# LEDBox.net
KiCad netlist of a schematic drawn in EAGLE
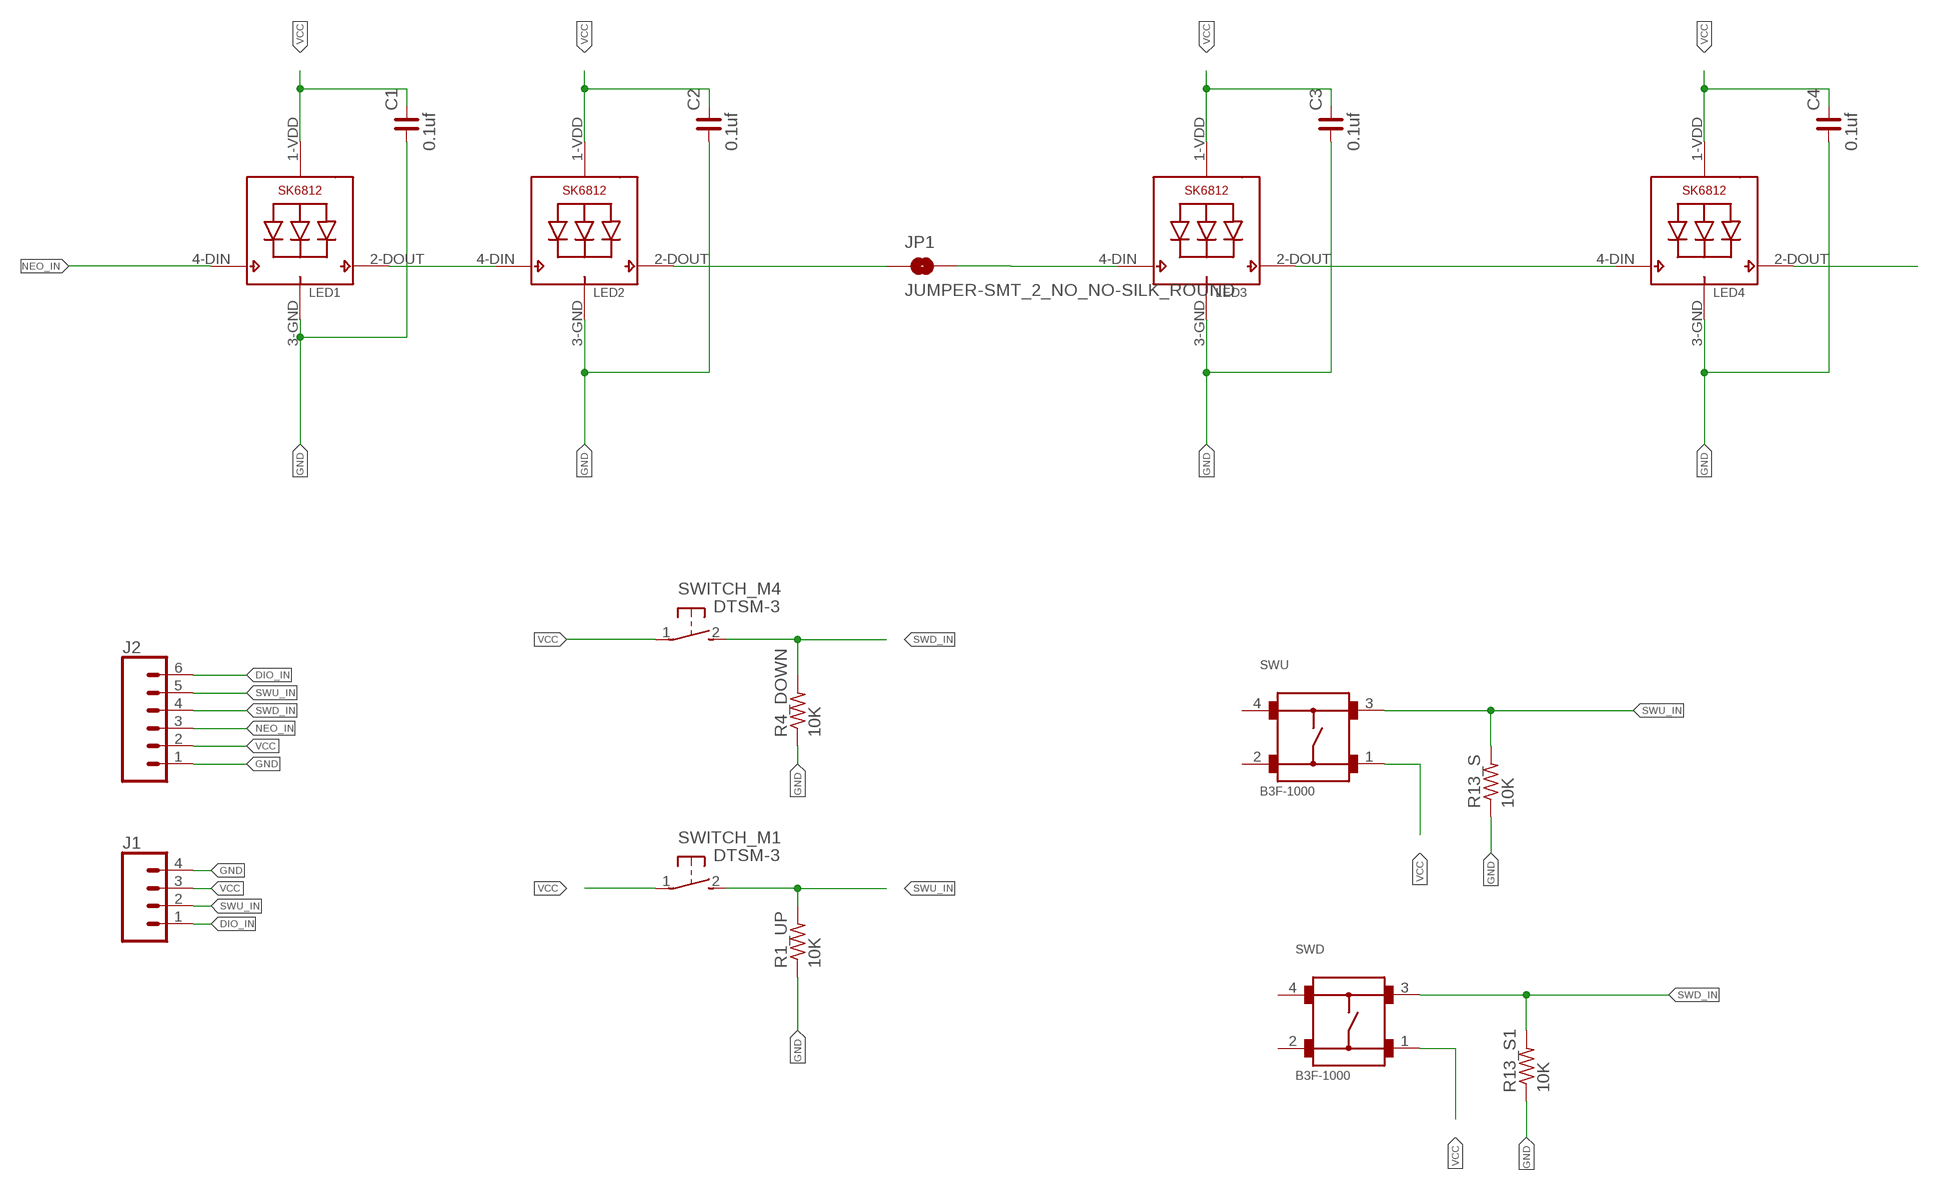
[diagram p0: schematic, sheet 1]

(export (version "E")
  (design (tool "Eeschema 10.0.6"))
  (components
    (comp (ref "C1")
      (value "0.1uf")
      (footprint "eagle-import:C0805")
      (libsource (lib "eagle-import") (part "C_0805"))
    )
    (comp (ref "C2")
      (value "0.1uf")
      (footprint "eagle-import:C0805")
      (libsource (lib "eagle-import") (part "C_0805"))
    )
    (comp (ref "C3")
      (value "0.1uf")
      (footprint "eagle-import:C0805")
      (libsource (lib "eagle-import") (part "C_0805"))
    )
    (comp (ref "C4")
      (value "0.1uf")
      (footprint "eagle-import:C0805")
      (libsource (lib "eagle-import") (part "C_0805"))
    )
    (comp (ref "J1")
      (value "CONN_041X04_NO_SILK")
      (footprint "eagle-import:1X04_NO_SILK")
      (libsource (lib "eagle-import") (part "CONN_041X04_NO_SILK"))
    )
    (comp (ref "J2")
      (value "CONN_06SMD-1MM")
      (footprint "eagle-import:1X06-1MM")
      (libsource (lib "eagle-import") (part "CONN_06SMD-1MM"))
    )
    (comp (ref "JP1")
      (value "JUMPER-SMT_2_NO_NO-SILK_ROUND")
      (footprint "eagle-import:SMT-JUMPER_2_NO_NO-SILK_ROUND")
      (libsource (lib "eagle-import") (part "JUMPER-SMT_2_NO_NO-SILK_ROUND"))
    )
    (comp (ref "LED1")
      (value "SK6812_5050W")
      (footprint "eagle-import:LED5050_W")
      (libsource (lib "eagle-import") (part "SK6812_5050W"))
    )
    (comp (ref "LED2")
      (value "SK6812_5050W")
      (footprint "eagle-import:LED5050_W")
      (libsource (lib "eagle-import") (part "SK6812_5050W"))
    )
    (comp (ref "LED3")
      (value "SK6812_5050W")
      (footprint "eagle-import:LED5050_W")
      (libsource (lib "eagle-import") (part "SK6812_5050W"))
    )
    (comp (ref "LED4")
      (value "SK6812_5050W")
      (footprint "eagle-import:LED5050_W")
      (libsource (lib "eagle-import") (part "SK6812_5050W"))
    )
    (comp (ref "R1_UP")
      (value "10K")
      (footprint "eagle-import:M0805")
      (libsource (lib "eagle-import") (part "R-US_M0805"))
    )
    (comp (ref "R4_DOWN")
      (value "10K")
      (footprint "eagle-import:M0805")
      (libsource (lib "eagle-import") (part "R-US_M0805"))
    )
    (comp (ref "R13_S")
      (value "10K")
      (footprint "eagle-import:M0805")
      (libsource (lib "eagle-import") (part "R-US_M0805"))
    )
    (comp (ref "R13_S1")
      (value "10K")
      (footprint "eagle-import:M0805")
      (libsource (lib "eagle-import") (part "R-US_M0805"))
    )
    (comp (ref "SWD")
      (value "B3F-1000")
      (footprint "eagle-import:B3F-1000")
      (fields
        (field (name "DIGI_KEY_PART_NUMBER") "SW400-ND")
        (field (name "MANUFACTURER") "Omron Electronics Inc-EMC Div")
        (field (name "CREATED_BY") "PCBLayout.com")
      )
      (libsource (lib "eagle-import") (part "B3F-1000"))
    )
    (comp (ref "SWITCH_M1")
      (value "DTSM-3")
      (footprint "eagle-import:DTSM-3")
      (libsource (lib "eagle-import") (part "DTSM-3"))
    )
    (comp (ref "SWITCH_M4")
      (value "DTSM-3")
      (footprint "eagle-import:DTSM-3")
      (libsource (lib "eagle-import") (part "DTSM-3"))
    )
    (comp (ref "SWU")
      (value "B3F-1000")
      (footprint "eagle-import:B3F-1000")
      (fields
        (field (name "DIGI_KEY_PART_NUMBER") "SW400-ND")
        (field (name "MANUFACTURER") "Omron Electronics Inc-EMC Div")
        (field (name "CREATED_BY") "PCBLayout.com")
      )
      (libsource (lib "eagle-import") (part "B3F-1000"))
    )
  )
  (nets
    (net (code "1") (name "DIO_IN") (class "Default")
      (node (ref "J1") (pin "1") (pinfunction "1_1") (pintype "passive"))
      (node (ref "J2") (pin "6") (pinfunction "6_6") (pintype "passive"))
    )
    (net (code "2") (name "GND") (class "Default")
      (node (ref "C1") (pin "1") (pinfunction "1_1") (pintype "passive"))
      (node (ref "C2") (pin "1") (pinfunction "1_1") (pintype "passive"))
      (node (ref "C3") (pin "1") (pinfunction "1_1") (pintype "passive"))
      (node (ref "C4") (pin "1") (pinfunction "1_1") (pintype "passive"))
      (node (ref "J1") (pin "4") (pinfunction "4_4") (pintype "passive"))
      (node (ref "J2") (pin "1") (pinfunction "1_1") (pintype "passive"))
      (node (ref "LED1") (pin "3-GND") (pinfunction "GND_3-GND") (pintype "power_in"))
      (node (ref "LED2") (pin "3-GND") (pinfunction "GND_3-GND") (pintype "power_in"))
      (node (ref "LED3") (pin "3-GND") (pinfunction "GND_3-GND") (pintype "power_in"))
      (node (ref "LED4") (pin "3-GND") (pinfunction "GND_3-GND") (pintype "power_in"))
      (node (ref "R13_S") (pin "1") (pinfunction "1_1") (pintype "passive"))
      (node (ref "R13_S1") (pin "1") (pinfunction "1_1") (pintype "passive"))
      (node (ref "R1_UP") (pin "1") (pinfunction "1_1") (pintype "passive"))
      (node (ref "R4_DOWN") (pin "1") (pinfunction "1_1") (pintype "passive"))
    )
    (net (code "3") (name "NEO_IN") (class "Default")
      (node (ref "J2") (pin "3") (pinfunction "3_3") (pintype "passive"))
      (node (ref "LED1") (pin "4-DIN") (pinfunction "DI_4-DIN") (pintype "input"))
    )
    (net (code "4") (name "Net-(LED1-DO)") (class "Default")
      (node (ref "LED1") (pin "2-DOUT") (pinfunction "DO_2-DOUT") (pintype "output"))
      (node (ref "LED2") (pin "4-DIN") (pinfunction "DI_4-DIN") (pintype "input"))
    )
    (net (code "5") (name "Net-(LED2-DO)") (class "Default")
      (node (ref "JP1") (pin "1") (pinfunction "1_1") (pintype "passive"))
      (node (ref "LED2") (pin "2-DOUT") (pinfunction "DO_2-DOUT") (pintype "output"))
    )
    (net (code "6") (name "Net-(LED3-DI)") (class "Default")
      (node (ref "JP1") (pin "2") (pinfunction "2_2") (pintype "passive"))
      (node (ref "LED3") (pin "4-DIN") (pinfunction "DI_4-DIN") (pintype "input"))
    )
    (net (code "7") (name "Net-(LED3-DO)") (class "Default")
      (node (ref "LED3") (pin "2-DOUT") (pinfunction "DO_2-DOUT") (pintype "output"))
      (node (ref "LED4") (pin "4-DIN") (pinfunction "DI_4-DIN") (pintype "input"))
    )
    (net (code "8") (name "SWD_IN") (class "Default")
      (node (ref "J2") (pin "4") (pinfunction "4_4") (pintype "passive"))
      (node (ref "R13_S1") (pin "2") (pinfunction "2_2") (pintype "passive"))
      (node (ref "R4_DOWN") (pin "2") (pinfunction "2_2") (pintype "passive"))
      (node (ref "SWD") (pin "3") (pinfunction "3_3") (pintype "passive"))
      (node (ref "SWITCH_M4") (pin "2") (pinfunction "2_2") (pintype "passive"))
    )
    (net (code "9") (name "SWU_IN") (class "Default")
      (node (ref "J1") (pin "2") (pinfunction "2_2") (pintype "passive"))
      (node (ref "J2") (pin "5") (pinfunction "5_5") (pintype "passive"))
      (node (ref "R13_S") (pin "2") (pinfunction "2_2") (pintype "passive"))
      (node (ref "R1_UP") (pin "2") (pinfunction "2_2") (pintype "passive"))
      (node (ref "SWITCH_M1") (pin "2") (pinfunction "2_2") (pintype "passive"))
      (node (ref "SWU") (pin "3") (pinfunction "3_3") (pintype "passive"))
    )
    (net (code "10") (name "VCC") (class "Default")
      (node (ref "C1") (pin "2") (pinfunction "2_2") (pintype "passive"))
      (node (ref "C2") (pin "2") (pinfunction "2_2") (pintype "passive"))
      (node (ref "C3") (pin "2") (pinfunction "2_2") (pintype "passive"))
      (node (ref "C4") (pin "2") (pinfunction "2_2") (pintype "passive"))
      (node (ref "J1") (pin "3") (pinfunction "3_3") (pintype "passive"))
      (node (ref "J2") (pin "2") (pinfunction "2_2") (pintype "passive"))
      (node (ref "LED1") (pin "1-VDD") (pinfunction "VDD_1-VDD") (pintype "power_in"))
      (node (ref "LED2") (pin "1-VDD") (pinfunction "VDD_1-VDD") (pintype "power_in"))
      (node (ref "LED3") (pin "1-VDD") (pinfunction "VDD_1-VDD") (pintype "power_in"))
      (node (ref "LED4") (pin "1-VDD") (pinfunction "VDD_1-VDD") (pintype "power_in"))
      (node (ref "SWD") (pin "1") (pinfunction "1_1") (pintype "passive"))
      (node (ref "SWITCH_M1") (pin "1") (pinfunction "1_1") (pintype "passive"))
      (node (ref "SWITCH_M4") (pin "1") (pinfunction "1_1") (pintype "passive"))
      (node (ref "SWU") (pin "1") (pinfunction "1_1") (pintype "passive"))
    )
    (net (code "11") (name "unconnected-(LED4-DO-Pad2-DOUT)") (class "Default")
      (node (ref "LED4") (pin "2-DOUT") (pinfunction "DO_2-DOUT") (pintype "output"))
    )
    (net (code "12") (name "unconnected-(SWD-Pad2)") (class "Default")
      (node (ref "SWD") (pin "2") (pinfunction "2_2") (pintype "passive"))
    )
    (net (code "13") (name "unconnected-(SWD-Pad4)") (class "Default")
      (node (ref "SWD") (pin "4") (pinfunction "4_4") (pintype "passive"))
    )
    (net (code "14") (name "unconnected-(SWU-Pad2)") (class "Default")
      (node (ref "SWU") (pin "2") (pinfunction "2_2") (pintype "passive"))
    )
    (net (code "15") (name "unconnected-(SWU-Pad4)") (class "Default")
      (node (ref "SWU") (pin "4") (pinfunction "4_4") (pintype "passive"))
    )
  )
)
